# Top_Bar.net
KiCad netlist of a schematic drawn in EAGLE
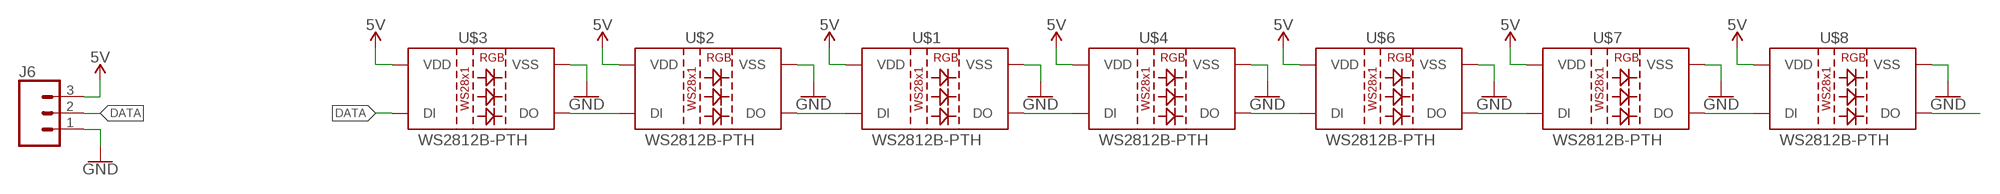
[diagram p0: schematic, sheet 1]

(export (version "E")
  (design (tool "Eeschema 10.0.6"))
  (components
    (comp (ref "J6")
      (value "CONN_03")
      (footprint "eagle-import:1X03")
      (libsource (lib "eagle-import") (part "CONN_03"))
    )
    (comp (ref "U$1")
      (value "WS2812B-PTH")
      (footprint "eagle-import:WS2812B-PTH-KIT")
      (libsource (lib "eagle-import") (part "WS2812B-PTH"))
    )
    (comp (ref "U$2")
      (value "WS2812B-PTH")
      (footprint "eagle-import:WS2812B-PTH-KIT")
      (libsource (lib "eagle-import") (part "WS2812B-PTH"))
    )
    (comp (ref "U$3")
      (value "WS2812B-PTH")
      (footprint "eagle-import:WS2812B-PTH-KIT")
      (libsource (lib "eagle-import") (part "WS2812B-PTH"))
    )
    (comp (ref "U$4")
      (value "WS2812B-PTH")
      (footprint "eagle-import:WS2812B-PTH-KIT")
      (libsource (lib "eagle-import") (part "WS2812B-PTH"))
    )
    (comp (ref "U$6")
      (value "WS2812B-PTH")
      (footprint "eagle-import:WS2812B-PTH-KIT")
      (libsource (lib "eagle-import") (part "WS2812B-PTH"))
    )
    (comp (ref "U$7")
      (value "WS2812B-PTH")
      (footprint "eagle-import:WS2812B-PTH-KIT")
      (libsource (lib "eagle-import") (part "WS2812B-PTH"))
    )
    (comp (ref "U$8")
      (value "WS2812B-PTH")
      (footprint "eagle-import:WS2812B-PTH-KIT")
      (libsource (lib "eagle-import") (part "WS2812B-PTH"))
    )
  )
  (nets
    (net (code "1") (name "5V") (class "Default")
      (node (ref "J6") (pin "3") (pinfunction "3_3") (pintype "passive"))
      (node (ref "U$1") (pin "2") (pinfunction "VDD_2") (pintype "bidirectional"))
      (node (ref "U$2") (pin "2") (pinfunction "VDD_2") (pintype "bidirectional"))
      (node (ref "U$3") (pin "2") (pinfunction "VDD_2") (pintype "bidirectional"))
      (node (ref "U$4") (pin "2") (pinfunction "VDD_2") (pintype "bidirectional"))
      (node (ref "U$6") (pin "2") (pinfunction "VDD_2") (pintype "bidirectional"))
      (node (ref "U$7") (pin "2") (pinfunction "VDD_2") (pintype "bidirectional"))
      (node (ref "U$8") (pin "2") (pinfunction "VDD_2") (pintype "bidirectional"))
    )
    (net (code "2") (name "DATA") (class "Default")
      (node (ref "J6") (pin "2") (pinfunction "2_2") (pintype "passive"))
      (node (ref "U$3") (pin "1") (pinfunction "DI_1") (pintype "bidirectional"))
    )
    (net (code "3") (name "GND") (class "Default")
      (node (ref "J6") (pin "1") (pinfunction "1_1") (pintype "passive"))
      (node (ref "U$1") (pin "3") (pinfunction "VSS_3") (pintype "bidirectional"))
      (node (ref "U$2") (pin "3") (pinfunction "VSS_3") (pintype "bidirectional"))
      (node (ref "U$3") (pin "3") (pinfunction "VSS_3") (pintype "bidirectional"))
      (node (ref "U$4") (pin "3") (pinfunction "VSS_3") (pintype "bidirectional"))
      (node (ref "U$6") (pin "3") (pinfunction "VSS_3") (pintype "bidirectional"))
      (node (ref "U$7") (pin "3") (pinfunction "VSS_3") (pintype "bidirectional"))
      (node (ref "U$8") (pin "3") (pinfunction "VSS_3") (pintype "bidirectional"))
    )
    (net (code "4") (name "Net-(U$1-DI)") (class "Default")
      (node (ref "U$1") (pin "1") (pinfunction "DI_1") (pintype "bidirectional"))
      (node (ref "U$2") (pin "4") (pinfunction "DO_4") (pintype "bidirectional"))
    )
    (net (code "5") (name "Net-(U$1-DO)") (class "Default")
      (node (ref "U$1") (pin "4") (pinfunction "DO_4") (pintype "bidirectional"))
      (node (ref "U$4") (pin "1") (pinfunction "DI_1") (pintype "bidirectional"))
    )
    (net (code "6") (name "Net-(U$2-DI)") (class "Default")
      (node (ref "U$2") (pin "1") (pinfunction "DI_1") (pintype "bidirectional"))
      (node (ref "U$3") (pin "4") (pinfunction "DO_4") (pintype "bidirectional"))
    )
    (net (code "7") (name "Net-(U$4-DO)") (class "Default")
      (node (ref "U$4") (pin "4") (pinfunction "DO_4") (pintype "bidirectional"))
      (node (ref "U$6") (pin "1") (pinfunction "DI_1") (pintype "bidirectional"))
    )
    (net (code "8") (name "Net-(U$6-DO)") (class "Default")
      (node (ref "U$6") (pin "4") (pinfunction "DO_4") (pintype "bidirectional"))
      (node (ref "U$7") (pin "1") (pinfunction "DI_1") (pintype "bidirectional"))
    )
    (net (code "9") (name "Net-(U$7-DO)") (class "Default")
      (node (ref "U$7") (pin "4") (pinfunction "DO_4") (pintype "bidirectional"))
      (node (ref "U$8") (pin "1") (pinfunction "DI_1") (pintype "bidirectional"))
    )
    (net (code "10") (name "unconnected-(U$8-DO-Pad4)") (class "Default")
      (node (ref "U$8") (pin "4") (pinfunction "DO_4") (pintype "bidirectional"))
    )
  )
)
